# esp32_module.net
KiCad netlist of a schematic drawn in EasyEDA
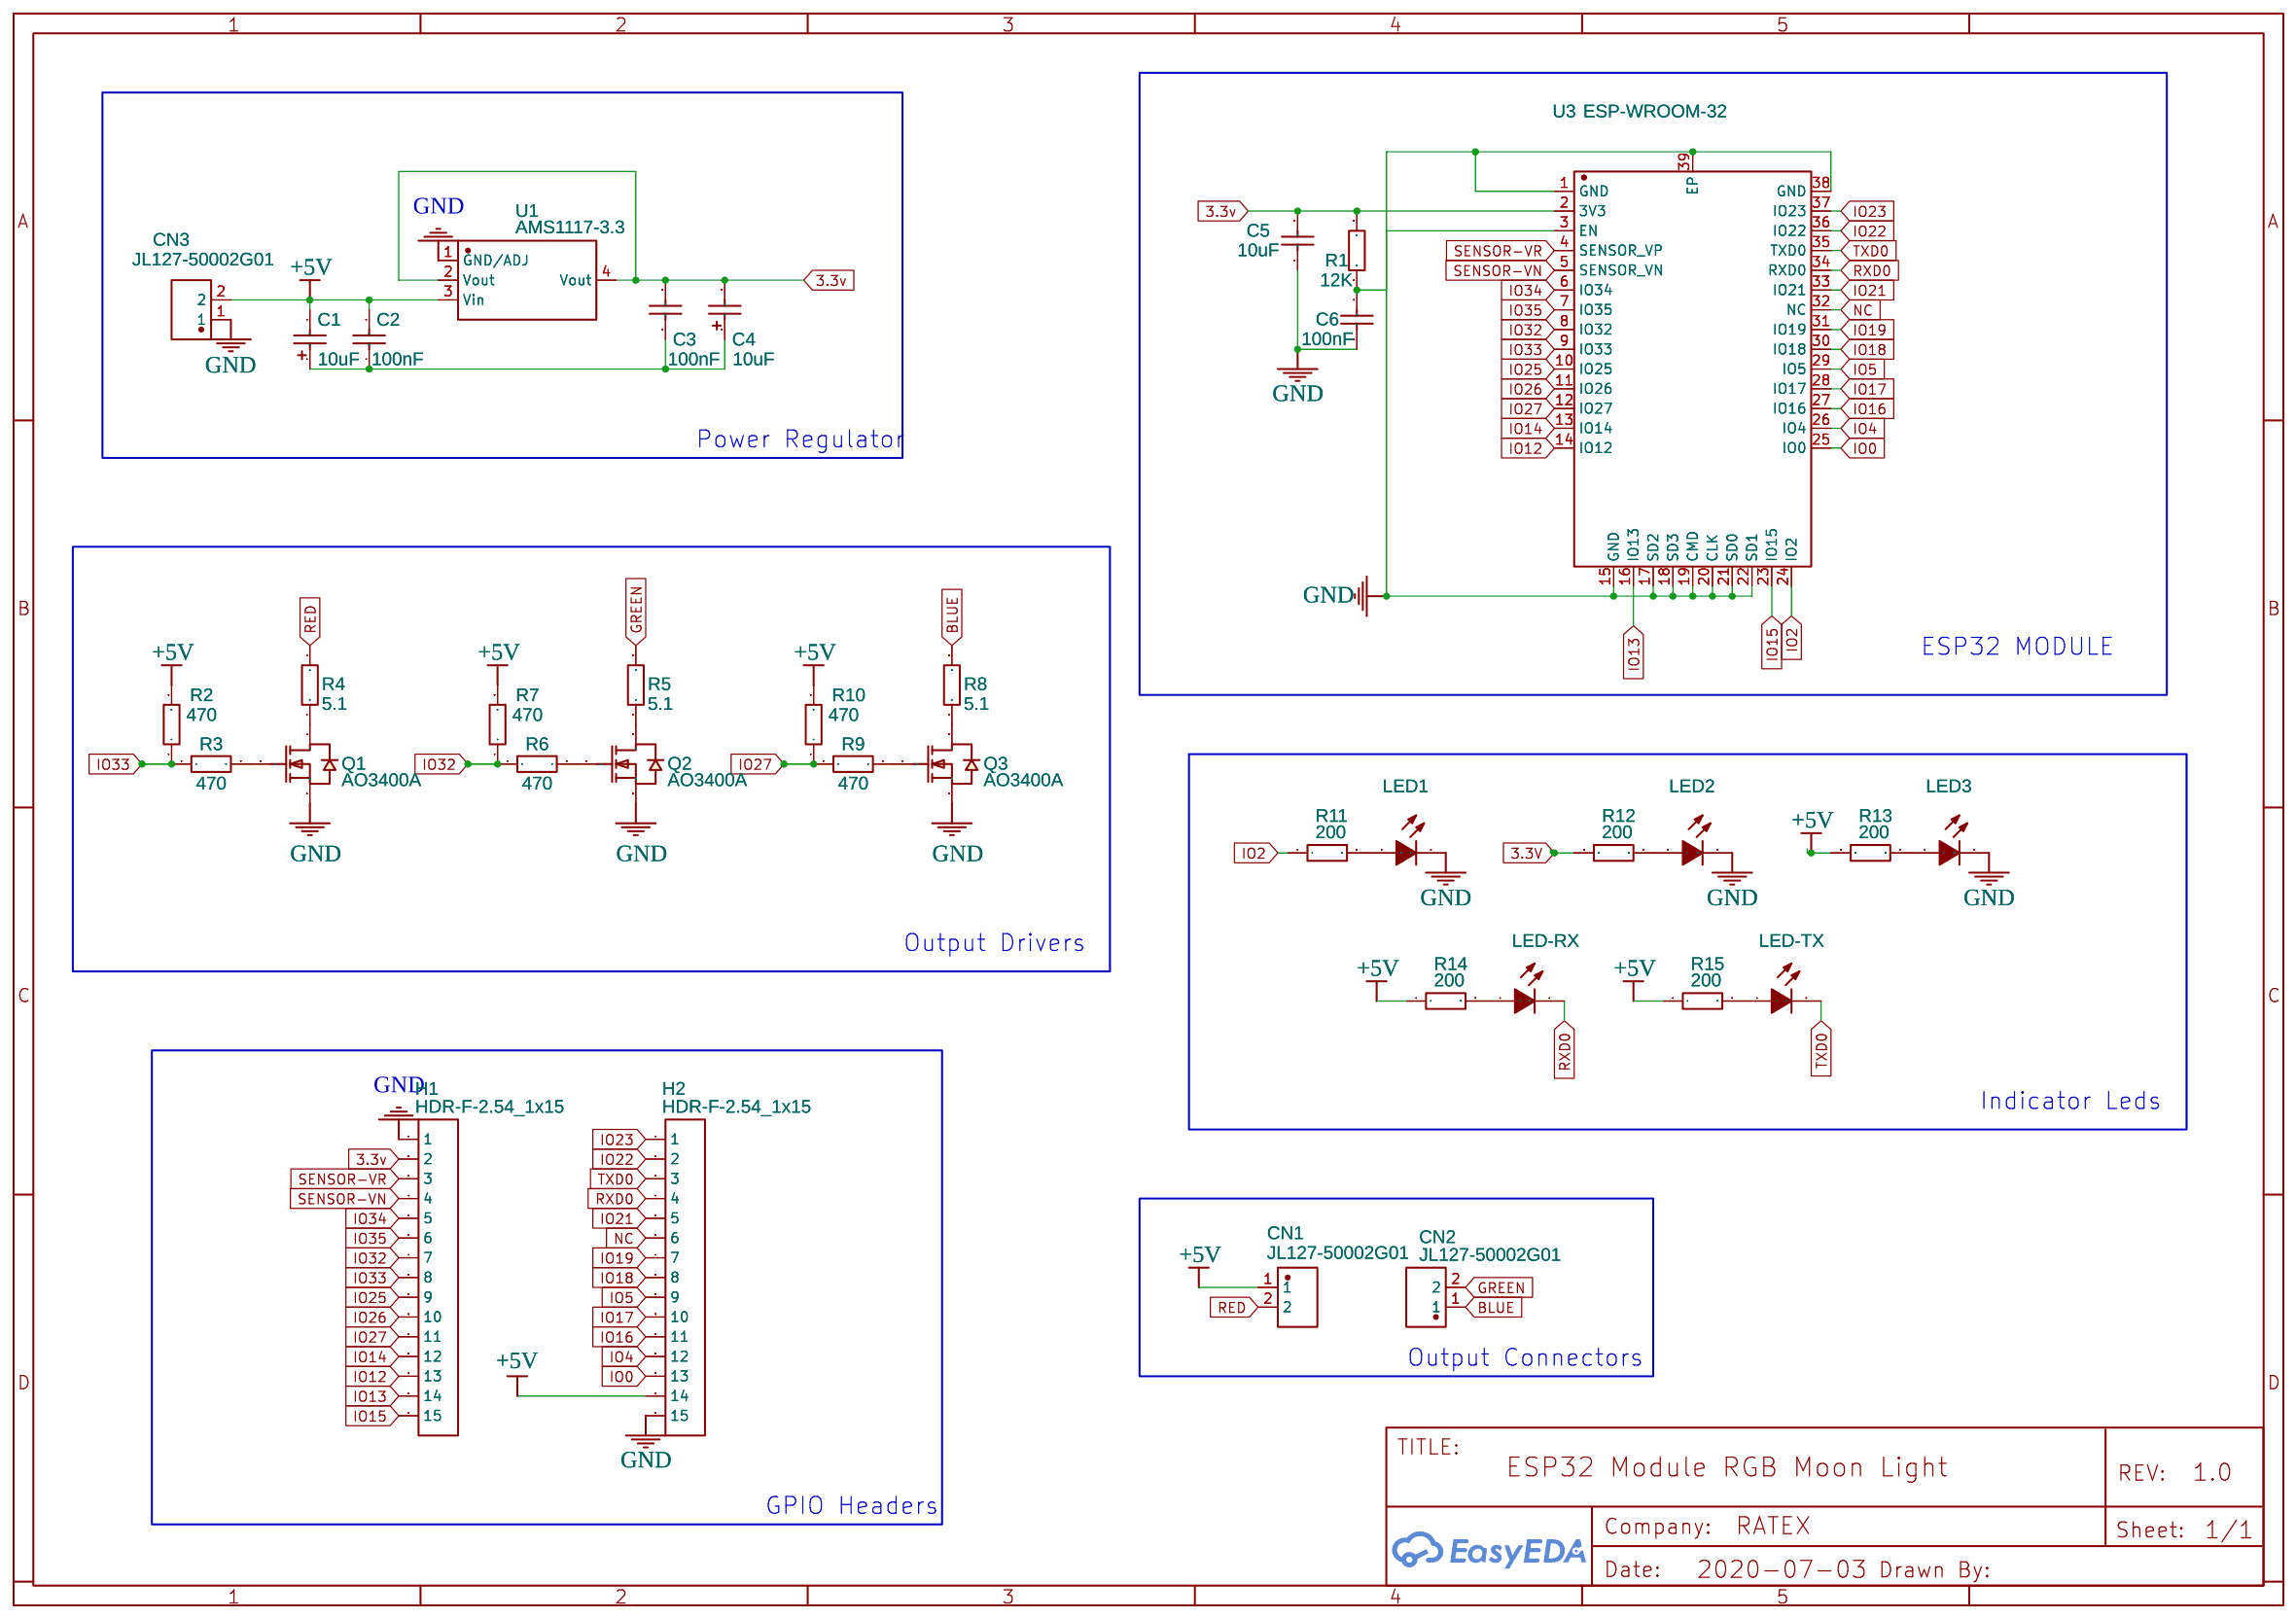
[diagram p0: schematic sheet]

(export (version "E")
  (design (tool "Eeschema 10.0.6"))
  (components
    (comp (ref "C1")
      (value "10uF")
      (fields
        (field (name "BOM_Manufacturer Part") "TAJA106K016RNJ")
        (field (name "BOM_Supplier Part") "C7171")
      )
      (libsource (lib "") (part "TAJA106K016RNJ"))
    )
    (comp (ref "C2")
      (value "100nF")
      (fields
        (field (name "BOM_Manufacturer Part") "CL05B104KO5NNNC")
        (field (name "BOM_Supplier Part") "C1525")
      )
      (libsource (lib "") (part "CL05B104KO5NNNC"))
    )
    (comp (ref "C3")
      (value "100nF")
      (fields
        (field (name "BOM_Manufacturer Part") "Calibration capacitor100nF（104）100V,5%")
        (field (name "BOM_Supplier Part") "C26609")
      )
      (libsource (lib "") (part "Calibration capacitor100nF（104）100V,5%"))
    )
    (comp (ref "C4")
      (value "10uF")
      (fields
        (field (name "BOM_Manufacturer Part") "TAJA106K016RNJ")
        (field (name "BOM_Supplier Part") "C7171")
      )
      (libsource (lib "") (part "TAJA106K016RNJ"))
    )
    (comp (ref "C5")
      (value "10uF")
      (fields
        (field (name "BOM_Manufacturer Part") "CL05A106MQ5NUNC")
        (field (name "BOM_Supplier Part") "C15525")
      )
      (libsource (lib "") (part "CL05A106MQ5NUNC"))
    )
    (comp (ref "C6")
      (value "100nF")
      (fields
        (field (name "BOM_Manufacturer Part") "CL05B104KO5NNNC")
        (field (name "BOM_Supplier Part") "C1525")
      )
      (libsource (lib "") (part "CL05B104KO5NNNC"))
    )
    (comp (ref "CN1")
      (value "JL127-50002G01")
      (fields (field (name "BOM_Supplier Part") "C387826"))
      (libsource (lib "") (part "JL127-50002G01"))
    )
    (comp (ref "CN2")
      (value "JL127-50002G01")
      (fields (field (name "BOM_Supplier Part") "C387826"))
      (libsource (lib "") (part "JL127-50002G01_1"))
    )
    (comp (ref "CN3")
      (value "JL127-50002G01")
      (fields (field (name "BOM_Supplier Part") "C387826"))
      (libsource (lib "") (part "JL127-50002G01_1"))
    )
    (comp (ref "H1")
      (value "HDR-F-2.54_1x15")
      (fields (field (name "BOM_Supplier Part") "C124408"))
      (libsource (lib "") (part "HDR-F-2.54_1x15"))
    )
    (comp (ref "H2")
      (value "HDR-F-2.54_1x15")
      (fields (field (name "BOM_Supplier Part") "C124408"))
      (libsource (lib "") (part "HDR-F-2.54_1x15"))
    )
    (comp (ref "LED-RX")
      (value "19-213/Y2C-CQ2R2L/3T(CY)")
      (fields (field (name "BOM_Supplier Part") "C72038"))
      (libsource (lib "") (part "19-213/Y2C-CQ2R2L/3T(CY)_2"))
    )
    (comp (ref "LED-TX")
      (value "19-213/Y2C-CQ2R2L/3T(CY)")
      (fields (field (name "BOM_Supplier Part") "C72038"))
      (libsource (lib "") (part "19-213/Y2C-CQ2R2L/3T(CY)_1"))
    )
    (comp (ref "LED1")
      (value "19-213/Y2C-CQ2R2L/3T(CY)")
      (fields (field (name "BOM_Supplier Part") "C72038"))
      (libsource (lib "") (part "19-213/Y2C-CQ2R2L/3T(CY)"))
    )
    (comp (ref "LED2")
      (value "19-213/Y2C-CQ2R2L/3T(CY)")
      (fields (field (name "BOM_Supplier Part") "C72038"))
      (libsource (lib "") (part "19-213/Y2C-CQ2R2L/3T(CY)"))
    )
    (comp (ref "LED3")
      (value "19-213/Y2C-CQ2R2L/3T(CY)")
      (fields (field (name "BOM_Supplier Part") "C72038"))
      (libsource (lib "") (part "19-213/Y2C-CQ2R2L/3T(CY)"))
    )
    (comp (ref "Q1")
      (value "AO3400A")
      (fields (field (name "BOM_Supplier Part") "C20917"))
      (libsource (lib "") (part "AO3400A"))
    )
    (comp (ref "Q2")
      (value "AO3400A")
      (fields (field (name "BOM_Supplier Part") "C20917"))
      (libsource (lib "") (part "AO3400A"))
    )
    (comp (ref "Q3")
      (value "AO3400A")
      (fields (field (name "BOM_Supplier Part") "C20917"))
      (libsource (lib "") (part "AO3400A"))
    )
    (comp (ref "R1")
      (value "12K")
      (fields
        (field (name "BOM_Manufacturer Part") "0402WGF1202TCE")
        (field (name "BOM_Supplier Part") "C25752")
      )
      (libsource (lib "") (part "0402WGF1202TCE"))
    )
    (comp (ref "R2")
      (value "470")
      (fields
        (field (name "BOM_Manufacturer Part") "0402WGF4700TCE")
        (field (name "BOM_Supplier Part") "C25117")
      )
      (libsource (lib "") (part "0402WGF4700TCE_1"))
    )
    (comp (ref "R3")
      (value "470")
      (fields
        (field (name "BOM_Manufacturer Part") "0402WGF4700TCE")
        (field (name "BOM_Supplier Part") "C25117")
      )
      (libsource (lib "") (part "0402WGF4700TCE"))
    )
    (comp (ref "R4")
      (value "5.1")
      (fields
        (field (name "BOM_Manufacturer Part") "25121WF510KT4E")
        (field (name "BOM_Supplier Part") "C73113")
      )
      (libsource (lib "") (part "25121WF510KT4E"))
    )
    (comp (ref "R5")
      (value "5.1")
      (fields
        (field (name "BOM_Manufacturer Part") "25121WF510KT4E")
        (field (name "BOM_Supplier Part") "C73113")
      )
      (libsource (lib "") (part "25121WF510KT4E"))
    )
    (comp (ref "R6")
      (value "470")
      (fields
        (field (name "BOM_Manufacturer Part") "0402WGF4700TCE")
        (field (name "BOM_Supplier Part") "C25117")
      )
      (libsource (lib "") (part "0402WGF4700TCE"))
    )
    (comp (ref "R7")
      (value "470")
      (fields
        (field (name "BOM_Manufacturer Part") "0402WGF4700TCE")
        (field (name "BOM_Supplier Part") "C25117")
      )
      (libsource (lib "") (part "0402WGF4700TCE_1"))
    )
    (comp (ref "R8")
      (value "5.1")
      (fields
        (field (name "BOM_Manufacturer Part") "25121WF510KT4E")
        (field (name "BOM_Supplier Part") "C73113")
      )
      (libsource (lib "") (part "25121WF510KT4E"))
    )
    (comp (ref "R9")
      (value "470")
      (fields
        (field (name "BOM_Manufacturer Part") "0402WGF4700TCE")
        (field (name "BOM_Supplier Part") "C25117")
      )
      (libsource (lib "") (part "0402WGF4700TCE"))
    )
    (comp (ref "R10")
      (value "470")
      (fields
        (field (name "BOM_Manufacturer Part") "0402WGF4700TCE")
        (field (name "BOM_Supplier Part") "C25117")
      )
      (libsource (lib "") (part "0402WGF4700TCE_1"))
    )
    (comp (ref "R11")
      (value "200")
      (fields
        (field (name "BOM_Manufacturer Part") "0402WGF2000TCE")
        (field (name "BOM_Supplier Part") "C25087")
      )
      (libsource (lib "") (part "0402WGF2000TCE"))
    )
    (comp (ref "R12")
      (value "200")
      (fields
        (field (name "BOM_Manufacturer Part") "0402WGF2000TCE")
        (field (name "BOM_Supplier Part") "C25087")
      )
      (libsource (lib "") (part "0402WGF2000TCE"))
    )
    (comp (ref "R13")
      (value "200")
      (fields
        (field (name "BOM_Manufacturer Part") "0402WGF2000TCE")
        (field (name "BOM_Supplier Part") "C25087")
      )
      (libsource (lib "") (part "0402WGF2000TCE"))
    )
    (comp (ref "R14")
      (value "200")
      (fields
        (field (name "BOM_Manufacturer Part") "0402WGF2000TCE")
        (field (name "BOM_Supplier Part") "C25087")
      )
      (libsource (lib "") (part "0402WGF2000TCE"))
    )
    (comp (ref "R15")
      (value "200")
      (fields
        (field (name "BOM_Manufacturer Part") "0402WGF2000TCE")
        (field (name "BOM_Supplier Part") "C25087")
      )
      (libsource (lib "") (part "0402WGF2000TCE"))
    )
    (comp (ref "U1")
      (value "AMS1117-3.3")
      (fields (field (name "BOM_Supplier Part") "C6186"))
      (libsource (lib "") (part "AMS1117-3.3"))
    )
    (comp (ref "U3")
      (value "ESP-WROOM-32")
      (fields (field (name "BOM_Supplier Part") "C95209"))
      (libsource (lib "") (part "ESP-WROOM-32"))
    )
  )
  (nets
    (net (code "1") (name "+5V") (class "Default")
      (node (ref "C2") (pin "2") (pinfunction "2_2") (pintype "input"))
      (node (ref "C4") (pin "2") (pinfunction "2_2") (pintype "input"))
      (node (ref "CN1") (pin "1") (pinfunction "1_1") (pintype "unspecified"))
      (node (ref "CN3") (pin "2") (pinfunction "2_2") (pintype "unspecified"))
      (node (ref "H2") (pin "14") (pinfunction "14_14") (pintype "unspecified"))
      (node (ref "R10") (pin "2") (pinfunction "2_2") (pintype "input"))
      (node (ref "R13") (pin "1") (pinfunction "1_1") (pintype "input"))
      (node (ref "R14") (pin "1") (pinfunction "1_1") (pintype "input"))
      (node (ref "R15") (pin "1") (pinfunction "1_1") (pintype "input"))
      (node (ref "R2") (pin "2") (pinfunction "2_2") (pintype "input"))
      (node (ref "R7") (pin "2") (pinfunction "2_2") (pintype "input"))
      (node (ref "U1") (pin "3") (pinfunction "Vin_3") (pintype "unspecified"))
    )
    (net (code "2") (name "3.3V") (class "Default")
      (node (ref "R12") (pin "1") (pinfunction "1_1") (pintype "input"))
    )
    (net (code "3") (name "3.3v") (class "Default")
      (node (ref "C1") (pin "2") (pinfunction "2_2") (pintype "input"))
      (node (ref "C3") (pin "2") (pinfunction "2_2") (pintype "input"))
      (node (ref "C5") (pin "2") (pinfunction "2_2") (pintype "input"))
      (node (ref "H1") (pin "2") (pinfunction "2_2") (pintype "unspecified"))
      (node (ref "R1") (pin "2") (pinfunction "2_2") (pintype "input"))
      (node (ref "U1") (pin "2") (pinfunction "Vout_2") (pintype "unspecified"))
      (node (ref "U1") (pin "4") (pinfunction "Vout_4") (pintype "unspecified"))
      (node (ref "U3") (pin "2") (pinfunction "3V3_2") (pintype "unspecified"))
    )
    (net (code "4") (name "BLUE") (class "Default")
      (node (ref "CN2") (pin "1") (pinfunction "1_1") (pintype "unspecified"))
      (node (ref "R8") (pin "2") (pinfunction "2_2") (pintype "unspecified"))
    )
    (net (code "5") (name "GND") (class "Default")
      (node (ref "C5") (pin "1") (pinfunction "1_1") (pintype "input"))
      (node (ref "C6") (pin "1") (pinfunction "1_1") (pintype "input"))
      (node (ref "CN3") (pin "1") (pinfunction "1_1") (pintype "unspecified"))
      (node (ref "H1") (pin "1") (pinfunction "1_1") (pintype "unspecified"))
      (node (ref "H2") (pin "15") (pinfunction "15_15") (pintype "unspecified"))
      (node (ref "LED1") (pin "2") (pinfunction "C_2") (pintype "input"))
      (node (ref "LED2") (pin "2") (pinfunction "C_2") (pintype "input"))
      (node (ref "LED3") (pin "2") (pinfunction "C_2") (pintype "input"))
      (node (ref "Q1") (pin "2") (pinfunction "S_2") (pintype "unspecified"))
      (node (ref "Q2") (pin "2") (pinfunction "S_2") (pintype "unspecified"))
      (node (ref "Q3") (pin "2") (pinfunction "S_2") (pintype "unspecified"))
      (node (ref "U1") (pin "1") (pinfunction "GND/ADJ_1") (pintype "unspecified"))
      (node (ref "U3") (pin "1") (pinfunction "GND_1") (pintype "unspecified"))
      (node (ref "U3") (pin "15") (pinfunction "GND_15") (pintype "unspecified"))
      (node (ref "U3") (pin "17") (pinfunction "SD2_17") (pintype "unspecified"))
      (node (ref "U3") (pin "18") (pinfunction "SD3_18") (pintype "unspecified"))
      (node (ref "U3") (pin "19") (pinfunction "CMD_19") (pintype "unspecified"))
      (node (ref "U3") (pin "20") (pinfunction "CLK_20") (pintype "unspecified"))
      (node (ref "U3") (pin "21") (pinfunction "SD0_21") (pintype "unspecified"))
      (node (ref "U3") (pin "22") (pinfunction "SD1_22") (pintype "unspecified"))
      (node (ref "U3") (pin "38") (pinfunction "GND_38") (pintype "unspecified"))
      (node (ref "U3") (pin "39") (pinfunction "EP_39") (pintype "unspecified"))
    )
    (net (code "6") (name "GREEN") (class "Default")
      (node (ref "CN2") (pin "2") (pinfunction "2_2") (pintype "unspecified"))
      (node (ref "R5") (pin "2") (pinfunction "2_2") (pintype "unspecified"))
    )
    (net (code "7") (name "IO0") (class "Default")
      (node (ref "H2") (pin "13") (pinfunction "13_13") (pintype "unspecified"))
      (node (ref "U3") (pin "25") (pinfunction "IO0_25") (pintype "unspecified"))
    )
    (net (code "8") (name "IO2") (class "Default")
      (node (ref "R11") (pin "1") (pinfunction "1_1") (pintype "input"))
      (node (ref "U3") (pin "24") (pinfunction "IO2_24") (pintype "unspecified"))
    )
    (net (code "9") (name "IO4") (class "Default")
      (node (ref "H2") (pin "12") (pinfunction "12_12") (pintype "unspecified"))
      (node (ref "U3") (pin "26") (pinfunction "IO4_26") (pintype "unspecified"))
    )
    (net (code "10") (name "IO5") (class "Default")
      (node (ref "H2") (pin "9") (pinfunction "9_9") (pintype "unspecified"))
      (node (ref "U3") (pin "29") (pinfunction "IO5_29") (pintype "unspecified"))
    )
    (net (code "11") (name "IO12") (class "Default")
      (node (ref "H1") (pin "13") (pinfunction "13_13") (pintype "unspecified"))
      (node (ref "U3") (pin "14") (pinfunction "IO12_14") (pintype "unspecified"))
    )
    (net (code "12") (name "IO13") (class "Default")
      (node (ref "H1") (pin "14") (pinfunction "14_14") (pintype "unspecified"))
      (node (ref "U3") (pin "16") (pinfunction "IO13_16") (pintype "unspecified"))
    )
    (net (code "13") (name "IO14") (class "Default")
      (node (ref "H1") (pin "12") (pinfunction "12_12") (pintype "unspecified"))
      (node (ref "U3") (pin "13") (pinfunction "IO14_13") (pintype "unspecified"))
    )
    (net (code "14") (name "IO15") (class "Default")
      (node (ref "H1") (pin "15") (pinfunction "15_15") (pintype "unspecified"))
      (node (ref "U3") (pin "23") (pinfunction "IO15_23") (pintype "unspecified"))
    )
    (net (code "15") (name "IO16") (class "Default")
      (node (ref "H2") (pin "11") (pinfunction "11_11") (pintype "unspecified"))
      (node (ref "U3") (pin "27") (pinfunction "IO16_27") (pintype "unspecified"))
    )
    (net (code "16") (name "IO17") (class "Default")
      (node (ref "H2") (pin "10") (pinfunction "10_10") (pintype "unspecified"))
      (node (ref "U3") (pin "28") (pinfunction "IO17_28") (pintype "unspecified"))
    )
    (net (code "17") (name "IO18") (class "Default")
      (node (ref "H2") (pin "8") (pinfunction "8_8") (pintype "unspecified"))
      (node (ref "U3") (pin "30") (pinfunction "IO18_30") (pintype "unspecified"))
    )
    (net (code "18") (name "IO19") (class "Default")
      (node (ref "H2") (pin "7") (pinfunction "7_7") (pintype "unspecified"))
      (node (ref "U3") (pin "31") (pinfunction "IO19_31") (pintype "unspecified"))
    )
    (net (code "19") (name "IO21") (class "Default")
      (node (ref "H2") (pin "5") (pinfunction "5_5") (pintype "unspecified"))
      (node (ref "U3") (pin "33") (pinfunction "IO21_33") (pintype "unspecified"))
    )
    (net (code "20") (name "IO22") (class "Default")
      (node (ref "H2") (pin "2") (pinfunction "2_2") (pintype "unspecified"))
      (node (ref "U3") (pin "36") (pinfunction "IO22_36") (pintype "unspecified"))
    )
    (net (code "21") (name "IO23") (class "Default")
      (node (ref "H2") (pin "1") (pinfunction "1_1") (pintype "unspecified"))
      (node (ref "U3") (pin "37") (pinfunction "IO23_37") (pintype "unspecified"))
    )
    (net (code "22") (name "IO25") (class "Default")
      (node (ref "H1") (pin "9") (pinfunction "9_9") (pintype "unspecified"))
      (node (ref "U3") (pin "10") (pinfunction "IO25_10") (pintype "unspecified"))
    )
    (net (code "23") (name "IO26") (class "Default")
      (node (ref "H1") (pin "10") (pinfunction "10_10") (pintype "unspecified"))
      (node (ref "U3") (pin "11") (pinfunction "IO26_11") (pintype "unspecified"))
    )
    (net (code "24") (name "IO27") (class "Default")
      (node (ref "H1") (pin "11") (pinfunction "11_11") (pintype "unspecified"))
      (node (ref "R10") (pin "1") (pinfunction "1_1") (pintype "input"))
      (node (ref "R9") (pin "1") (pinfunction "1_1") (pintype "input"))
      (node (ref "U3") (pin "12") (pinfunction "IO27_12") (pintype "unspecified"))
    )
    (net (code "25") (name "IO32") (class "Default")
      (node (ref "H1") (pin "7") (pinfunction "7_7") (pintype "unspecified"))
      (node (ref "R6") (pin "1") (pinfunction "1_1") (pintype "input"))
      (node (ref "R7") (pin "1") (pinfunction "1_1") (pintype "input"))
      (node (ref "U3") (pin "8") (pinfunction "IO32_8") (pintype "unspecified"))
    )
    (net (code "26") (name "IO33") (class "Default")
      (node (ref "H1") (pin "8") (pinfunction "8_8") (pintype "unspecified"))
      (node (ref "R2") (pin "1") (pinfunction "1_1") (pintype "input"))
      (node (ref "R3") (pin "1") (pinfunction "1_1") (pintype "input"))
      (node (ref "U3") (pin "9") (pinfunction "IO33_9") (pintype "unspecified"))
    )
    (net (code "27") (name "IO34") (class "Default")
      (node (ref "H1") (pin "5") (pinfunction "5_5") (pintype "unspecified"))
      (node (ref "U3") (pin "6") (pinfunction "IO34_6") (pintype "unspecified"))
    )
    (net (code "28") (name "IO35") (class "Default")
      (node (ref "H1") (pin "6") (pinfunction "6_6") (pintype "unspecified"))
      (node (ref "U3") (pin "7") (pinfunction "IO35_7") (pintype "unspecified"))
    )
    (net (code "29") (name "NC") (class "Default")
      (node (ref "H2") (pin "6") (pinfunction "6_6") (pintype "unspecified"))
      (node (ref "U3") (pin "32") (pinfunction "NC_32") (pintype "unspecified"))
    )
    (net (code "30") (name "Net-(C1-Pad1)") (class "Default")
      (node (ref "C1") (pin "1") (pinfunction "1_1") (pintype "input"))
      (node (ref "C2") (pin "1") (pinfunction "1_1") (pintype "input"))
      (node (ref "C3") (pin "1") (pinfunction "1_1") (pintype "input"))
      (node (ref "C4") (pin "1") (pinfunction "1_1") (pintype "input"))
    )
    (net (code "31") (name "Net-(LED-RX-A)") (class "Default")
      (node (ref "LED-RX") (pin "1") (pinfunction "A_1") (pintype "input"))
      (node (ref "R14") (pin "2") (pinfunction "2_2") (pintype "input"))
    )
    (net (code "32") (name "Net-(LED-TX-A)") (class "Default")
      (node (ref "LED-TX") (pin "1") (pinfunction "A_1") (pintype "input"))
      (node (ref "R15") (pin "2") (pinfunction "2_2") (pintype "input"))
    )
    (net (code "33") (name "Net-(LED1-A)") (class "Default")
      (node (ref "LED1") (pin "1") (pinfunction "A_1") (pintype "input"))
      (node (ref "R11") (pin "2") (pinfunction "2_2") (pintype "input"))
    )
    (net (code "34") (name "Net-(LED2-A)") (class "Default")
      (node (ref "LED2") (pin "1") (pinfunction "A_1") (pintype "input"))
      (node (ref "R12") (pin "2") (pinfunction "2_2") (pintype "input"))
    )
    (net (code "35") (name "Net-(LED3-A)") (class "Default")
      (node (ref "LED3") (pin "1") (pinfunction "A_1") (pintype "input"))
      (node (ref "R13") (pin "2") (pinfunction "2_2") (pintype "input"))
    )
    (net (code "36") (name "Net-(Q1-D)") (class "Default")
      (node (ref "Q1") (pin "3") (pinfunction "D_3") (pintype "unspecified"))
      (node (ref "R4") (pin "1") (pinfunction "1_1") (pintype "unspecified"))
    )
    (net (code "37") (name "Net-(Q1-G)") (class "Default")
      (node (ref "Q1") (pin "1") (pinfunction "G_1") (pintype "unspecified"))
      (node (ref "R3") (pin "2") (pinfunction "2_2") (pintype "input"))
    )
    (net (code "38") (name "Net-(Q2-D)") (class "Default")
      (node (ref "Q2") (pin "3") (pinfunction "D_3") (pintype "unspecified"))
      (node (ref "R5") (pin "1") (pinfunction "1_1") (pintype "unspecified"))
    )
    (net (code "39") (name "Net-(Q2-G)") (class "Default")
      (node (ref "Q2") (pin "1") (pinfunction "G_1") (pintype "unspecified"))
      (node (ref "R6") (pin "2") (pinfunction "2_2") (pintype "input"))
    )
    (net (code "40") (name "Net-(Q3-D)") (class "Default")
      (node (ref "Q3") (pin "3") (pinfunction "D_3") (pintype "unspecified"))
      (node (ref "R8") (pin "1") (pinfunction "1_1") (pintype "unspecified"))
    )
    (net (code "41") (name "Net-(Q3-G)") (class "Default")
      (node (ref "Q3") (pin "1") (pinfunction "G_1") (pintype "unspecified"))
      (node (ref "R9") (pin "2") (pinfunction "2_2") (pintype "input"))
    )
    (net (code "42") (name "Net-(U3-EN)") (class "Default")
      (node (ref "C6") (pin "2") (pinfunction "2_2") (pintype "input"))
      (node (ref "R1") (pin "1") (pinfunction "1_1") (pintype "input"))
      (node (ref "U3") (pin "3") (pinfunction "EN_3") (pintype "unspecified"))
    )
    (net (code "43") (name "RED") (class "Default")
      (node (ref "CN1") (pin "2") (pinfunction "2_2") (pintype "unspecified"))
      (node (ref "R4") (pin "2") (pinfunction "2_2") (pintype "unspecified"))
    )
    (net (code "44") (name "RXD0") (class "Default")
      (node (ref "H2") (pin "4") (pinfunction "4_4") (pintype "unspecified"))
      (node (ref "LED-RX") (pin "2") (pinfunction "C_2") (pintype "input"))
      (node (ref "U3") (pin "34") (pinfunction "RXD0_34") (pintype "unspecified"))
    )
    (net (code "45") (name "SENSOR-VN") (class "Default")
      (node (ref "H1") (pin "4") (pinfunction "4_4") (pintype "unspecified"))
      (node (ref "U3") (pin "5") (pinfunction "SENSOR_VN_5") (pintype "unspecified"))
    )
    (net (code "46") (name "SENSOR-VR") (class "Default")
      (node (ref "H1") (pin "3") (pinfunction "3_3") (pintype "unspecified"))
      (node (ref "U3") (pin "4") (pinfunction "SENSOR_VP_4") (pintype "unspecified"))
    )
    (net (code "47") (name "TXD0") (class "Default")
      (node (ref "H2") (pin "3") (pinfunction "3_3") (pintype "unspecified"))
      (node (ref "LED-TX") (pin "2") (pinfunction "C_2") (pintype "input"))
      (node (ref "U3") (pin "35") (pinfunction "TXD0_35") (pintype "unspecified"))
    )
  )
)
